# IMU.net
KiCad netlist of a schematic drawn in Altium Designer
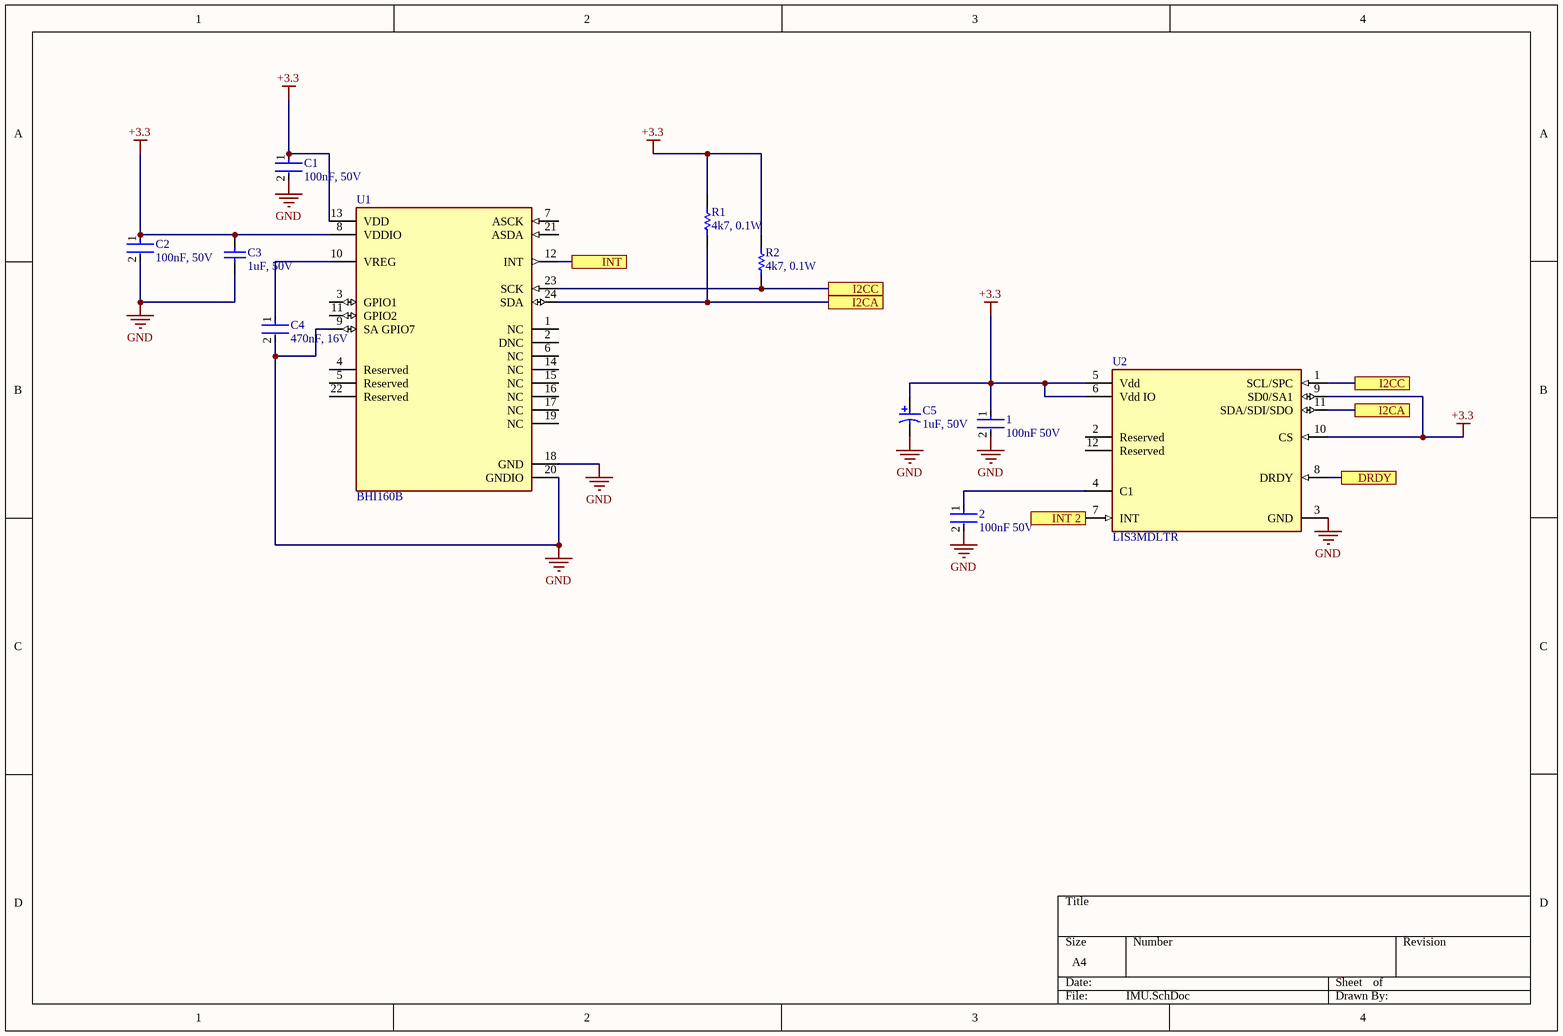
[diagram p0: IMU.SchDoc]

(export (version "E")
  (design (tool "Eeschema 10.0.6"))
  (components
    (comp (ref "1")
      (value "100nF 50V")
      (footprint "FP-CGA3E-0_3-0_1-IPC_A")
      (description "Cap Ceramic 100nF 50V X7R 10% Pad SMD 0603 +125°C Automotive T/R")
      (fields (field (name "TOLERANCE") "10%") (field (name "VOLTAGE") "50V"))
      (libsource (lib "Altium Content Vault") (part "b4654b650e69147ec39a6b967a45e02"))
    )
    (comp (ref "2")
      (value "100nF 50V")
      (footprint "FP-CGA3E-0_3-0_1-IPC_A")
      (description "Cap Ceramic 100nF 50V X7R 10% Pad SMD 0603 +125°C Automotive T/R")
      (fields (field (name "TOLERANCE") "10%") (field (name "VOLTAGE") "50V"))
      (libsource (lib "Altium Content Vault") (part "b4654b650e69147ec39a6b967a45e02"))
    )
    (comp (ref "C1")
      (value "100nF, 50V")
      (footprint "FP-CGA3E-0_3-0_1-IPC_A")
      (description "Cap Ceramic 100nF 50V X7R 10% Pad SMD 0603 +125°C Automotive T/R")
      (fields (field (name "TOLERANCE") "10%") (field (name "VOLTAGE") "50V"))
      (libsource (lib "Altium Content Vault") (part "b4654b650e69147ec39a6b967a45e02"))
    )
    (comp (ref "C2")
      (value "100nF, 50V")
      (footprint "FP-CGA3E-0_3-0_1-IPC_A")
      (description "Cap Ceramic 100nF 50V X7R 10% Pad SMD 0603 +125°C Automotive T/R")
      (fields (field (name "TOLERANCE") "10%") (field (name "VOLTAGE") "50V"))
      (libsource (lib "Altium Content Vault") (part "b4654b650e69147ec39a6b967a45e02"))
    )
    (comp (ref "C3")
      (value "1uF, 50V")
      (footprint "CAPC1608X90X35ML10T25")
      (description "Chip Capacitor, 1 uF, +/- 10%, 50 V, -55 to 85 degC, 0603 (1608 Metric), RoHS, Tape and Reel")
      (fields (field (name "TOLERANCE") "±10%") (field (name "MANUFACTURER") "Taiyo Yuden"))
      (libsource (lib "Altium Content Vault") (part "CAP-NP-2"))
    )
    (comp (ref "C4")
      (value "470nF, 16V")
      (footprint "FP-C0603C-CF-MFG")
      (description "CAP CER 0.47UF 16V X7R 0603")
      (fields (field (name "TOLERANCE") "0.1") (field (name "MANUFACTURER PART NUMBER") "C0603C474K4RACTU"))
      (libsource (lib "Altium Content Vault") (part "b4654b650e69147ec39a6b967a45e02"))
    )
    (comp (ref "C5")
      (value "1uF, 50V")
      (footprint "CAPPR55-200-1100X500X1200")
      (description "Aluminum Electrolytic Capacitor, 1 uF, +/- 20%, 50 V, -55 to 105 degC, 2-Pin THD, RoHS, Bulk")
      (libsource (lib "Altium Content Vault") (part "CAP-P-2"))
    )
    (comp (ref "R1")
      (value "4k7, 0.1W")
      (footprint "RESC1608X55X25LL10T15")
      (description "Chip Resistor, 4.7 KOhm, +/- 1%, 0.1 W, -55 to 155 degC, 0603 (1608 Metric), RoHS, Tape and Reel")
      (fields (field (name "MANUFACTURER") "Yageo") (field (name "TOLERANCE") "1%"))
      (libsource (lib "Altium Content Vault") (part "RES-2"))
    )
    (comp (ref "R2")
      (value "4k7, 0.1W")
      (footprint "RESC1608X55X25LL10T15")
      (description "Chip Resistor, 4.7 KOhm, +/- 1%, 0.1 W, -55 to 155 degC, 0603 (1608 Metric), RoHS, Tape and Reel")
      (fields (field (name "MANUFACTURER") "Yageo") (field (name "TOLERANCE") "1%"))
      (libsource (lib "Altium Content Vault") (part "RES-2"))
    )
    (comp (ref "U1")
      (value "BHI160B")
      (footprint "FP-BHI160B-MFG")
      (description "IMU ACCEL/GYRO 3-AXIS I2C 24LGA")
      (fields
        (field (name "OCTOPART") "https://octopart.com/bhi160b-bosch+sensortec-108216126")
        (field (name "MANUFACTURER") "Bosch Sensortec")
      )
      (libsource (lib "Altium Content Vault") (part "2d8cd2e68e3e323d24208bb39551349"))
    )
    (comp (ref "U2")
      (value "LIS3MDLTR")
      (footprint "FP-VFLGA-12-8365767-MFG")
      (description "SENSOR MR I2C/SPI 12LGA")
      (fields
        (field (name "OCTOPART") "https://octopart.com/lis3mdltr-stmicroelectronics-29403125")
        (field (name "MANUFACTURER") "STMicroelectronics")
      )
      (libsource (lib "Altium Content Vault") (part "41c0331d4207a07573b21020ef49d7d"))
    )
  )
  (nets
    (net (code "1") (name "+3.3") (class "Default")
      (node (ref "1") (pin "1") (pinfunction "1_1") (pintype "passive"))
      (node (ref "C1") (pin "1") (pinfunction "1_1") (pintype "passive"))
      (node (ref "C2") (pin "1") (pinfunction "1_1") (pintype "passive"))
      (node (ref "C3") (pin "2") (pinfunction "2_2") (pintype "passive"))
      (node (ref "C5") (pin "1") (pinfunction "1_1") (pintype "passive"))
      (node (ref "R1") (pin "2") (pinfunction "2_2") (pintype "passive"))
      (node (ref "R2") (pin "2") (pinfunction "2_2") (pintype "passive"))
      (node (ref "U1") (pin "13") (pinfunction "VDD_13") (pintype "power_in"))
      (node (ref "U1") (pin "8") (pinfunction "VDDIO_8") (pintype "power_in"))
      (node (ref "U2") (pin "10") (pinfunction "CS_10") (pintype "input"))
      (node (ref "U2") (pin "5") (pinfunction "Vdd_5") (pintype "power_in"))
      (node (ref "U2") (pin "6") (pinfunction "Vdd_IO_6") (pintype "power_in"))
      (node (ref "U2") (pin "9") (pinfunction "SD0/SA1_9") (pintype "bidirectional"))
    )
    (net (code "2") (name "/DRDY") (class "Default")
      (node (ref "U2") (pin "8") (pinfunction "DRDY_8") (pintype "input"))
    )
    (net (code "3") (name "/I2CA") (class "Default")
      (node (ref "R1") (pin "1") (pinfunction "1_1") (pintype "passive"))
      (node (ref "U1") (pin "24") (pinfunction "SDA_24") (pintype "bidirectional"))
      (node (ref "U2") (pin "11") (pinfunction "SDA/SDI/SDO_11") (pintype "bidirectional"))
    )
    (net (code "4") (name "/I2CC") (class "Default")
      (node (ref "R2") (pin "1") (pinfunction "1_1") (pintype "passive"))
      (node (ref "U1") (pin "23") (pinfunction "SCK_23") (pintype "input"))
      (node (ref "U2") (pin "1") (pinfunction "SCL/SPC_1") (pintype "input"))
    )
    (net (code "5") (name "/INT") (class "Default")
      (node (ref "U1") (pin "12") (pinfunction "INT_12") (pintype "output"))
    )
    (net (code "6") (name "/INT 2") (class "Default")
      (node (ref "U2") (pin "7") (pinfunction "INT_7") (pintype "input"))
    )
    (net (code "7") (name "GND") (class "Default")
      (node (ref "1") (pin "2") (pinfunction "2_2") (pintype "passive"))
      (node (ref "2") (pin "2") (pinfunction "2_2") (pintype "passive"))
      (node (ref "C1") (pin "2") (pinfunction "2_2") (pintype "passive"))
      (node (ref "C2") (pin "2") (pinfunction "2_2") (pintype "passive"))
      (node (ref "C3") (pin "1") (pinfunction "1_1") (pintype "passive"))
      (node (ref "C4") (pin "2") (pinfunction "2_2") (pintype "passive"))
      (node (ref "C5") (pin "2") (pinfunction "2_2") (pintype "passive"))
      (node (ref "U1") (pin "18") (pinfunction "GND_18") (pintype "power_in"))
      (node (ref "U1") (pin "20") (pinfunction "GNDIO_20") (pintype "power_in"))
      (node (ref "U1") (pin "9") (pinfunction "SA_GPIO7_9") (pintype "bidirectional"))
      (node (ref "U2") (pin "3") (pinfunction "GND_3") (pintype "power_in"))
    )
    (net (code "8") (name "Net-(U1-VREG)") (class "Default")
      (node (ref "C4") (pin "1") (pinfunction "1_1") (pintype "passive"))
      (node (ref "U1") (pin "10") (pinfunction "VREG_10") (pintype "passive"))
    )
    (net (code "9") (name "Net-(U2-C1)") (class "Default")
      (node (ref "2") (pin "1") (pinfunction "1_1") (pintype "passive"))
      (node (ref "U2") (pin "4") (pinfunction "C1_4") (pintype "passive"))
    )
    (net (code "10") (name "unconnected-(U1-ASCK-Pad7)") (class "Default")
      (node (ref "U1") (pin "7") (pinfunction "ASCK_7") (pintype "input"))
    )
    (net (code "11") (name "unconnected-(U1-ASDA-Pad21)") (class "Default")
      (node (ref "U1") (pin "21") (pinfunction "ASDA_21") (pintype "input"))
    )
    (net (code "12") (name "unconnected-(U1-DNC-Pad2)") (class "Default")
      (node (ref "U1") (pin "2") (pinfunction "DNC_2") (pintype "passive"))
    )
    (net (code "13") (name "unconnected-(U1-GPIO1-Pad3)") (class "Default")
      (node (ref "U1") (pin "3") (pinfunction "GPIO1_3") (pintype "bidirectional"))
    )
    (net (code "14") (name "unconnected-(U1-GPIO2-Pad11)") (class "Default")
      (node (ref "U1") (pin "11") (pinfunction "GPIO2_11") (pintype "bidirectional"))
    )
    (net (code "15") (name "unconnected-(U1-NC-Pad1)") (class "Default")
      (node (ref "U1") (pin "1") (pinfunction "NC_1") (pintype "passive"))
    )
    (net (code "16") (name "unconnected-(U1-NC-Pad6)") (class "Default")
      (node (ref "U1") (pin "6") (pinfunction "NC_6") (pintype "passive"))
    )
    (net (code "17") (name "unconnected-(U1-NC-Pad14)") (class "Default")
      (node (ref "U1") (pin "14") (pinfunction "NC_14") (pintype "passive"))
    )
    (net (code "18") (name "unconnected-(U1-NC-Pad15)") (class "Default")
      (node (ref "U1") (pin "15") (pinfunction "NC_15") (pintype "passive"))
    )
    (net (code "19") (name "unconnected-(U1-NC-Pad16)") (class "Default")
      (node (ref "U1") (pin "16") (pinfunction "NC_16") (pintype "passive"))
    )
    (net (code "20") (name "unconnected-(U1-NC-Pad17)") (class "Default")
      (node (ref "U1") (pin "17") (pinfunction "NC_17") (pintype "passive"))
    )
    (net (code "21") (name "unconnected-(U1-NC-Pad19)") (class "Default")
      (node (ref "U1") (pin "19") (pinfunction "NC_19") (pintype "passive"))
    )
    (net (code "22") (name "unconnected-(U1-Reserved-Pad4)") (class "Default")
      (node (ref "U1") (pin "4") (pinfunction "Reserved_4") (pintype "passive"))
    )
    (net (code "23") (name "unconnected-(U1-Reserved-Pad5)") (class "Default")
      (node (ref "U1") (pin "5") (pinfunction "Reserved_5") (pintype "passive"))
    )
    (net (code "24") (name "unconnected-(U1-Reserved-Pad22)") (class "Default")
      (node (ref "U1") (pin "22") (pinfunction "Reserved_22") (pintype "passive"))
    )
    (net (code "25") (name "unconnected-(U2-Reserved-Pad2)") (class "Default")
      (node (ref "U2") (pin "2") (pinfunction "Reserved_2") (pintype "passive"))
    )
    (net (code "26") (name "unconnected-(U2-Reserved-Pad12)") (class "Default")
      (node (ref "U2") (pin "12") (pinfunction "Reserved_12") (pintype "passive"))
    )
  )
)
